# Astromereni_05.net
KiCad netlist of a schematic drawn in EAGLE
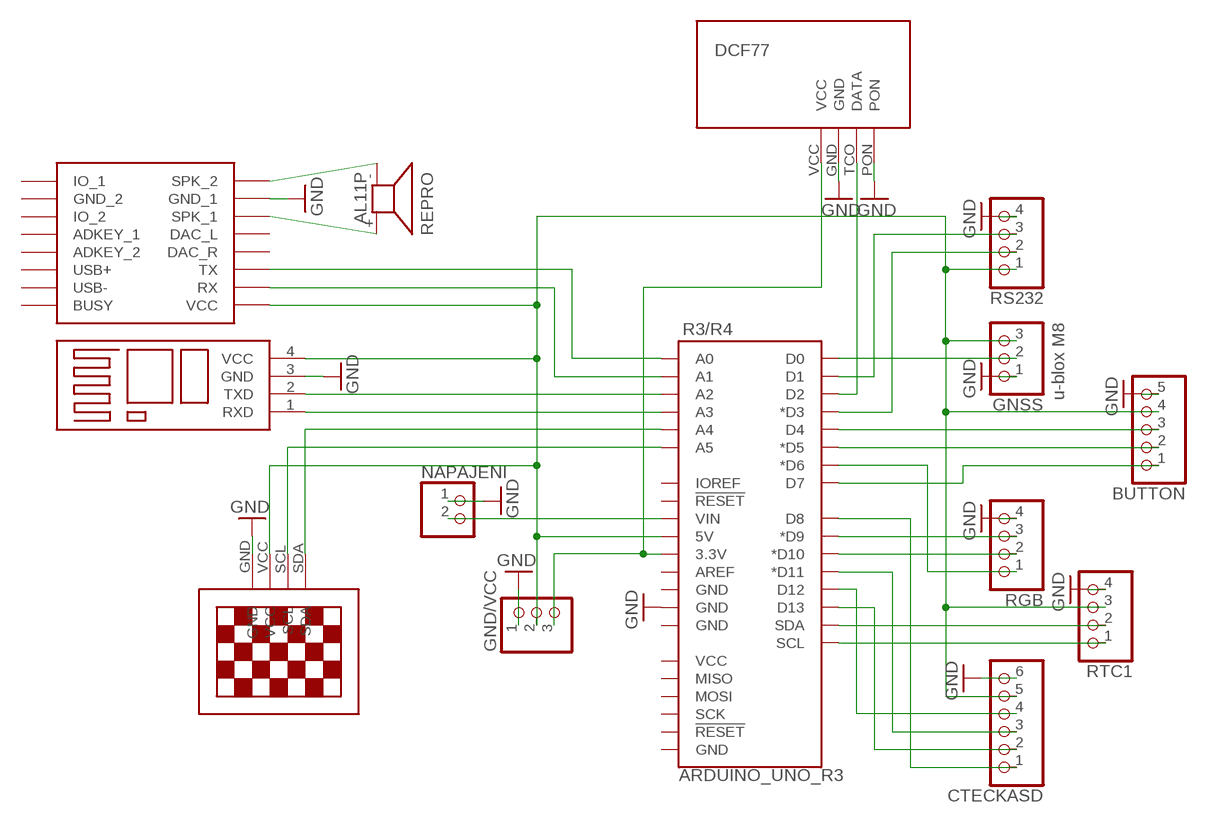
[diagram p0: schematic, sheet 1]

(export (version "E")
  (design (tool "Eeschema 10.0.6"))
  (components
    (comp (ref "B4")
      (value "BLUETOOTH")
      (footprint "eagle-import:BLUETOOTH")
      (libsource (lib "eagle-import") (part "BLUETOOTH"))
    )
    (comp (ref "BUTTON")
      (value "PINHD-1X5")
      (footprint "eagle-import:1X05")
      (libsource (lib "eagle-import") (part "PINHD-1X5"))
    )
    (comp (ref "CTECKASD")
      (value "PINHD-1X6")
      (footprint "eagle-import:1X06")
      (libsource (lib "eagle-import") (part "PINHD-1X6"))
    )
    (comp (ref "GND/VCC")
      (value "PINHD-1X3")
      (footprint "eagle-import:1X03")
      (libsource (lib "eagle-import") (part "PINHD-1X3"))
    )
    (comp (ref "GNSS")
      (value "PINHD-1X3")
      (footprint "eagle-import:1X03")
      (libsource (lib "eagle-import") (part "PINHD-1X3"))
    )
    (comp (ref "NAPAJENI")
      (value "PINHD-1X2")
      (footprint "eagle-import:1X02")
      (libsource (lib "eagle-import") (part "PINHD-1X2"))
    )
    (comp (ref "R3/R4")
      (value "ARDUINO_UNO_R3")
      (footprint "eagle-import:ARDUINO_R3")
      (libsource (lib "eagle-import") (part "ARDUINO_UNO_R3"))
    )
    (comp (ref "REPRO")
      (value "AL11P")
      (footprint "eagle-import:AL11P")
      (libsource (lib "eagle-import") (part "AL11P"))
    )
    (comp (ref "RGB")
      (value "PINHD-1X4")
      (footprint "eagle-import:1X04")
      (libsource (lib "eagle-import") (part "PINHD-1X4"))
    )
    (comp (ref "RS232")
      (value "PINHD-1X4")
      (footprint "eagle-import:1X04")
      (libsource (lib "eagle-import") (part "PINHD-1X4"))
    )
    (comp (ref "RTC1")
      (value "PINHD-1X4")
      (footprint "eagle-import:1X04")
      (libsource (lib "eagle-import") (part "PINHD-1X4"))
    )
    (comp (ref "U$3")
      (value "DFPLAYER")
      (footprint "eagle-import:DFPLAYER")
      (libsource (lib "eagle-import") (part "DFPLAYER"))
    )
    (comp (ref "U$5")
      (value "13\"OLED13\"OLED")
      (footprint "eagle-import:1.3_OLED")
      (libsource (lib "eagle-import") (part "13{dblquote}OLED13{dblquote}OLED"))
    )
    (comp (ref "U$6")
      (value "DCF77")
      (footprint "eagle-import:DCF77")
      (libsource (lib "eagle-import") (part "DCF77"))
    )
  )
  (nets
    (net (code "1") (name "GND") (class "Default")
      (node (ref "B4") (pin "3") (pinfunction "GND_3") (pintype "power_in"))
      (node (ref "BUTTON") (pin "5") (pinfunction "5_5") (pintype "passive"))
      (node (ref "CTECKASD") (pin "6") (pinfunction "6_6") (pintype "passive"))
      (node (ref "GND/VCC") (pin "1") (pinfunction "1_1") (pintype "passive"))
      (node (ref "GNSS") (pin "1") (pinfunction "1_1") (pintype "passive"))
      (node (ref "NAPAJENI") (pin "1") (pinfunction "1_1") (pintype "passive"))
      (node (ref "R3/R4") (pin "GND@3") (pinfunction "GND_GND@3") (pintype "bidirectional"))
      (node (ref "RGB") (pin "4") (pinfunction "4_4") (pintype "passive"))
      (node (ref "RS232") (pin "4") (pinfunction "4_4") (pintype "passive"))
      (node (ref "RTC1") (pin "4") (pinfunction "4_4") (pintype "passive"))
      (node (ref "U$3") (pin "GND_1") (pinfunction "GND_1_GND_1") (pintype "bidirectional"))
      (node (ref "U$5") (pin "GND") (pinfunction "GND_GND") (pintype "bidirectional"))
      (node (ref "U$6") (pin "GND") (pinfunction "GND_GND") (pintype "bidirectional"))
      (node (ref "U$6") (pin "PON") (pinfunction "PON_PON") (pintype "bidirectional"))
    )
    (net (code "2") (name "Net-(B4-RXD)") (class "Default")
      (node (ref "B4") (pin "1") (pinfunction "RXD_1") (pintype "bidirectional"))
      (node (ref "R3/R4") (pin "A3") (pinfunction "A3_A3") (pintype "bidirectional"))
    )
    (net (code "3") (name "Net-(B4-TXD)") (class "Default")
      (node (ref "B4") (pin "2") (pinfunction "TXD_2") (pintype "bidirectional"))
      (node (ref "R3/R4") (pin "A2") (pinfunction "A2_A2") (pintype "bidirectional"))
    )
    (net (code "4") (name "Net-(B4-VCC)") (class "Default")
      (node (ref "B4") (pin "4") (pinfunction "VCC_4") (pintype "power_in"))
      (node (ref "BUTTON") (pin "4") (pinfunction "4_4") (pintype "passive"))
      (node (ref "CTECKASD") (pin "5") (pinfunction "5_5") (pintype "passive"))
      (node (ref "GND/VCC") (pin "2") (pinfunction "2_2") (pintype "passive"))
      (node (ref "GNSS") (pin "3") (pinfunction "3_3") (pintype "passive"))
      (node (ref "R3/R4") (pin "5V") (pinfunction "5V_5V") (pintype "bidirectional"))
      (node (ref "RS232") (pin "1") (pinfunction "1_1") (pintype "passive"))
      (node (ref "RTC1") (pin "3") (pinfunction "3_3") (pintype "passive"))
      (node (ref "U$3") (pin "VCC") (pinfunction "VCC_VCC") (pintype "bidirectional"))
      (node (ref "U$5") (pin "VCC") (pinfunction "VCC_VCC") (pintype "bidirectional"))
    )
    (net (code "5") (name "Net-(BUTTON-Pad1)") (class "Default")
      (node (ref "BUTTON") (pin "1") (pinfunction "1_1") (pintype "passive"))
      (node (ref "R3/R4") (pin "D7") (pinfunction "D7_D7") (pintype "bidirectional"))
    )
    (net (code "6") (name "Net-(BUTTON-Pad3)") (class "Default")
      (node (ref "BUTTON") (pin "3") (pinfunction "3_3") (pintype "passive"))
      (node (ref "R3/R4") (pin "D4") (pinfunction "D4_D4") (pintype "bidirectional"))
    )
    (net (code "7") (name "Net-(CTECKASD-Pad1)") (class "Default")
      (node (ref "CTECKASD") (pin "1") (pinfunction "1_1") (pintype "passive"))
      (node (ref "R3/R4") (pin "D8") (pinfunction "D8_D8") (pintype "bidirectional"))
    )
    (net (code "8") (name "Net-(CTECKASD-Pad2)") (class "Default")
      (node (ref "CTECKASD") (pin "2") (pinfunction "2_2") (pintype "passive"))
      (node (ref "R3/R4") (pin "D13") (pinfunction "D13_D13") (pintype "bidirectional"))
    )
    (net (code "9") (name "Net-(CTECKASD-Pad4)") (class "Default")
      (node (ref "CTECKASD") (pin "4") (pinfunction "4_4") (pintype "passive"))
      (node (ref "R3/R4") (pin "D12") (pinfunction "D12_D12") (pintype "bidirectional"))
    )
    (net (code "10") (name "Net-(GND/VCC-Pad3)") (class "Default")
      (node (ref "GND/VCC") (pin "3") (pinfunction "3_3") (pintype "passive"))
      (node (ref "R3/R4") (pin "3.3V") (pinfunction "3.3V_3.3V") (pintype "bidirectional"))
      (node (ref "U$6") (pin "VCC") (pinfunction "VCC_VCC") (pintype "power_in"))
    )
    (net (code "11") (name "Net-(GNSS-Pad2)") (class "Default")
      (node (ref "GNSS") (pin "2") (pinfunction "2_2") (pintype "passive"))
      (node (ref "R3/R4") (pin "D0") (pinfunction "D0_D0") (pintype "bidirectional"))
    )
    (net (code "12") (name "Net-(NAPAJENI-Pad2)") (class "Default")
      (node (ref "NAPAJENI") (pin "2") (pinfunction "2_2") (pintype "passive"))
      (node (ref "R3/R4") (pin "VIN") (pinfunction "VIN_VIN") (pintype "bidirectional"))
    )
    (net (code "13") (name "Net-(R3/R4-*D3)") (class "Default")
      (node (ref "R3/R4") (pin "D3") (pinfunction "*D3_D3") (pintype "bidirectional"))
      (node (ref "RS232") (pin "2") (pinfunction "2_2") (pintype "passive"))
    )
    (net (code "14") (name "Net-(R3/R4-*D5)") (class "Default")
      (node (ref "BUTTON") (pin "2") (pinfunction "2_2") (pintype "passive"))
      (node (ref "R3/R4") (pin "D5") (pinfunction "*D5_D5") (pintype "bidirectional"))
    )
    (net (code "15") (name "Net-(R3/R4-*D6)") (class "Default")
      (node (ref "R3/R4") (pin "D6") (pinfunction "*D6_D6") (pintype "bidirectional"))
      (node (ref "RGB") (pin "1") (pinfunction "1_1") (pintype "passive"))
    )
    (net (code "16") (name "Net-(R3/R4-*D9)") (class "Default")
      (node (ref "R3/R4") (pin "D9") (pinfunction "*D9_D9") (pintype "bidirectional"))
      (node (ref "RGB") (pin "3") (pinfunction "3_3") (pintype "passive"))
    )
    (net (code "17") (name "Net-(R3/R4-*D10)") (class "Default")
      (node (ref "R3/R4") (pin "D10") (pinfunction "*D10_D10") (pintype "bidirectional"))
      (node (ref "RGB") (pin "2") (pinfunction "2_2") (pintype "passive"))
    )
    (net (code "18") (name "Net-(R3/R4-*D11)") (class "Default")
      (node (ref "CTECKASD") (pin "3") (pinfunction "3_3") (pintype "passive"))
      (node (ref "R3/R4") (pin "D11") (pinfunction "*D11_D11") (pintype "bidirectional"))
    )
    (net (code "19") (name "Net-(R3/R4-PadA0)") (class "Default")
      (node (ref "R3/R4") (pin "A0") (pinfunction "A0_A0") (pintype "bidirectional"))
      (node (ref "U$3") (pin "TX") (pinfunction "TX_TX") (pintype "bidirectional"))
    )
    (net (code "20") (name "Net-(R3/R4-PadA1)") (class "Default")
      (node (ref "R3/R4") (pin "A1") (pinfunction "A1_A1") (pintype "bidirectional"))
      (node (ref "U$3") (pin "RX") (pinfunction "RX_RX") (pintype "bidirectional"))
    )
    (net (code "21") (name "Net-(R3/R4-PadA4)") (class "Default")
      (node (ref "R3/R4") (pin "A4") (pinfunction "A4_A4") (pintype "bidirectional"))
      (node (ref "U$5") (pin "SDA") (pinfunction "SDA_SDA") (pintype "bidirectional"))
    )
    (net (code "22") (name "Net-(R3/R4-PadA5)") (class "Default")
      (node (ref "R3/R4") (pin "A5") (pinfunction "A5_A5") (pintype "bidirectional"))
      (node (ref "U$5") (pin "SCL") (pinfunction "SCL_SCL") (pintype "bidirectional"))
    )
    (net (code "23") (name "Net-(R3/R4-PadD1)") (class "Default")
      (node (ref "R3/R4") (pin "D1") (pinfunction "D1_D1") (pintype "bidirectional"))
      (node (ref "RS232") (pin "3") (pinfunction "3_3") (pintype "passive"))
    )
    (net (code "24") (name "Net-(R3/R4-PadSCL)") (class "Default")
      (node (ref "R3/R4") (pin "SCL") (pinfunction "SCL_SCL") (pintype "bidirectional"))
      (node (ref "RTC1") (pin "1") (pinfunction "1_1") (pintype "passive"))
    )
    (net (code "25") (name "Net-(R3/R4-PadSDA)") (class "Default")
      (node (ref "R3/R4") (pin "SDA") (pinfunction "SDA_SDA") (pintype "bidirectional"))
      (node (ref "RTC1") (pin "2") (pinfunction "2_2") (pintype "passive"))
    )
    (net (code "26") (name "Net-(REPRO-1)") (class "Default")
      (node (ref "REPRO") (pin "-") (pinfunction "1_-") (pintype "passive"))
      (node (ref "U$3") (pin "SPK2") (pinfunction "SPK_2_SPK2") (pintype "bidirectional"))
    )
    (net (code "27") (name "Net-(REPRO-2)") (class "Default")
      (node (ref "REPRO") (pin "+") (pinfunction "2_+") (pintype "passive"))
      (node (ref "U$3") (pin "SPK1") (pinfunction "SPK_1_SPK1") (pintype "bidirectional"))
    )
    (net (code "28") (name "Net-(U$6-DATA)") (class "Default")
      (node (ref "R3/R4") (pin "D2") (pinfunction "D2_D2") (pintype "bidirectional"))
      (node (ref "U$6") (pin "TCO") (pinfunction "DATA_TCO") (pintype "output"))
    )
    (net (code "29") (name "unconnected-(R3/R4-GND-PadGND@1)") (class "Default")
      (node (ref "R3/R4") (pin "GND@1") (pinfunction "GND_GND@1") (pintype "bidirectional"))
    )
    (net (code "30") (name "unconnected-(R3/R4-GND-PadGND@2)") (class "Default")
      (node (ref "R3/R4") (pin "GND@2") (pinfunction "GND_GND@2") (pintype "bidirectional"))
    )
    (net (code "31") (name "unconnected-(R3/R4-GND-PadGND@4)") (class "Default")
      (node (ref "R3/R4") (pin "GND@4") (pinfunction "GND_GND@4") (pintype "bidirectional"))
    )
    (net (code "32") (name "unconnected-(R3/R4-PadAREF)") (class "Default")
      (node (ref "R3/R4") (pin "AREF") (pinfunction "AREF_AREF") (pintype "bidirectional"))
    )
    (net (code "33") (name "unconnected-(R3/R4-PadIOREF)") (class "Default")
      (node (ref "R3/R4") (pin "IOREF") (pinfunction "IOREF_IOREF") (pintype "bidirectional"))
    )
    (net (code "34") (name "unconnected-(R3/R4-PadMISO)") (class "Default")
      (node (ref "R3/R4") (pin "MISO") (pinfunction "MISO_MISO") (pintype "bidirectional"))
    )
    (net (code "35") (name "unconnected-(R3/R4-PadMOSI)") (class "Default")
      (node (ref "R3/R4") (pin "MOSI") (pinfunction "MOSI_MOSI") (pintype "bidirectional"))
    )
    (net (code "36") (name "unconnected-(R3/R4-PadSCK)") (class "Default")
      (node (ref "R3/R4") (pin "SCK") (pinfunction "SCK_SCK") (pintype "bidirectional"))
    )
    (net (code "37") (name "unconnected-(R3/R4-PadVCC)") (class "Default")
      (node (ref "R3/R4") (pin "VCC") (pinfunction "VCC_VCC") (pintype "bidirectional"))
    )
    (net (code "38") (name "unconnected-(R3/R4-~{RESET}-PadRESET@1)") (class "Default")
      (node (ref "R3/R4") (pin "RESET@1") (pinfunction "~{RESET}_RESET@1") (pintype "bidirectional"))
    )
    (net (code "39") (name "unconnected-(R3/R4-~{RESET}-PadRESET@2)") (class "Default")
      (node (ref "R3/R4") (pin "RESET@2") (pinfunction "~{RESET}_RESET@2") (pintype "bidirectional"))
    )
    (net (code "40") (name "unconnected-(U$3-ADKEY_1-PadADKEY1)") (class "Default")
      (node (ref "U$3") (pin "ADKEY1") (pinfunction "ADKEY_1_ADKEY1") (pintype "bidirectional"))
    )
    (net (code "41") (name "unconnected-(U$3-ADKEY_2-PadADKEY2)") (class "Default")
      (node (ref "U$3") (pin "ADKEY2") (pinfunction "ADKEY_2_ADKEY2") (pintype "bidirectional"))
    )
    (net (code "42") (name "unconnected-(U$3-IO_1-PadIO1)") (class "Default")
      (node (ref "U$3") (pin "IO1") (pinfunction "IO_1_IO1") (pintype "bidirectional"))
    )
    (net (code "43") (name "unconnected-(U$3-IO_2-PadIO2)") (class "Default")
      (node (ref "U$3") (pin "IO2") (pinfunction "IO_2_IO2") (pintype "bidirectional"))
    )
    (net (code "44") (name "unconnected-(U$3-PadBUSY)") (class "Default")
      (node (ref "U$3") (pin "BUSY") (pinfunction "BUSY_BUSY") (pintype "bidirectional"))
    )
    (net (code "45") (name "unconnected-(U$3-PadDAC_L)") (class "Default")
      (node (ref "U$3") (pin "DAC_L") (pinfunction "DAC_L_DAC_L") (pintype "bidirectional"))
    )
    (net (code "46") (name "unconnected-(U$3-PadDAC_R)") (class "Default")
      (node (ref "U$3") (pin "DAC_R") (pinfunction "DAC_R_DAC_R") (pintype "bidirectional"))
    )
    (net (code "47") (name "unconnected-(U$3-PadGND_2)") (class "Default")
      (node (ref "U$3") (pin "GND_2") (pinfunction "GND_2_GND_2") (pintype "bidirectional"))
    )
    (net (code "48") (name "unconnected-(U$3-PadUSB+)") (class "Default")
      (node (ref "U$3") (pin "USB+") (pinfunction "USB+_USB+") (pintype "bidirectional"))
    )
    (net (code "49") (name "unconnected-(U$3-PadUSB-)") (class "Default")
      (node (ref "U$3") (pin "USB-") (pinfunction "USB-_USB-") (pintype "bidirectional"))
    )
  )
)
